# Digispark_Neopixel_Button_Cycler.net
KiCad netlist of a schematic drawn in EAGLE
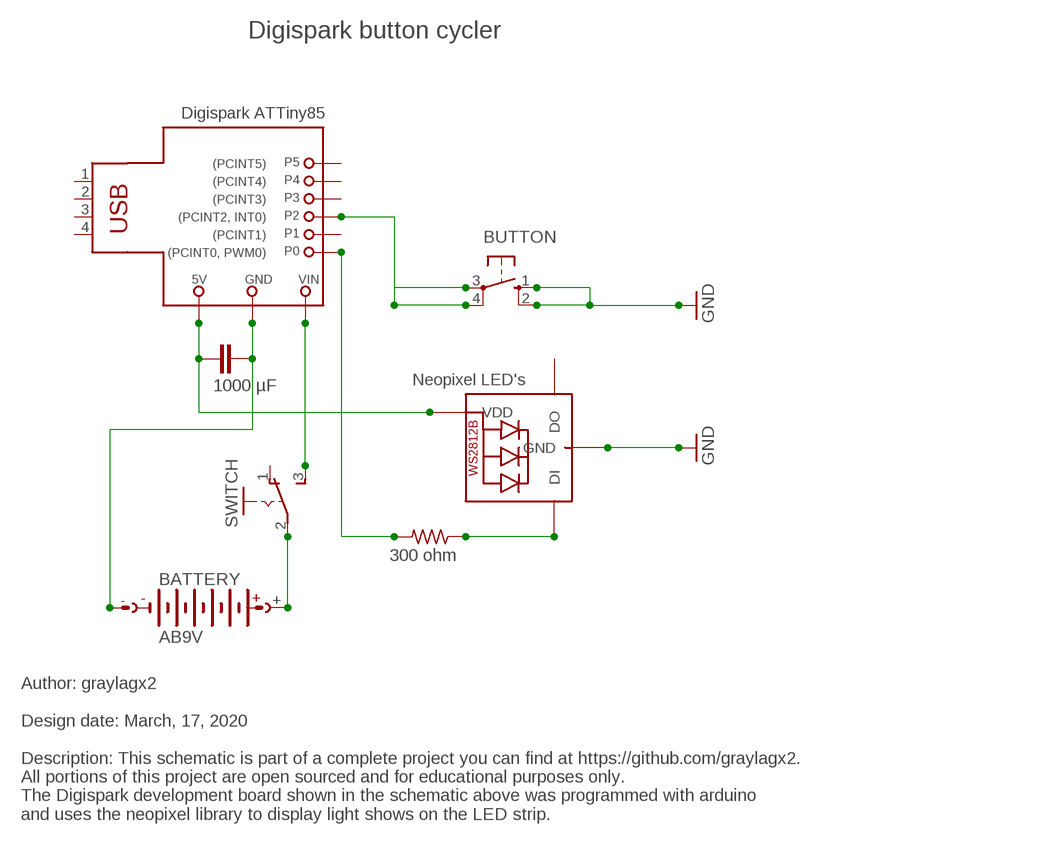
[diagram p0: schematic, sheet 1]

(export (version "E")
  (design (tool "Eeschema 10.0.6"))
  (components
    (comp (ref "BATTERY")
      (value "AB9V")
      (footprint "eagle-import:AB9V")
      (libsource (lib "eagle-import") (part "AB9V"))
    )
    (comp (ref "BUTTON")
      (value "10-XX")
      (footprint "eagle-import:B3F-10XX")
      (fields (field (name "MPN") "B3F-1000"))
      (libsource (lib "eagle-import") (part "10-XX"))
    )
    (comp (ref "C1")
      (value "1000 µF")
      (footprint "eagle-import:C2.5-2")
      (libsource (lib "eagle-import") (part "C2.5/2"))
    )
    (comp (ref "LED1")
      (value "WS2812B5050")
      (footprint "eagle-import:WS2812B")
      (libsource (lib "eagle-import") (part "WS2812B5050"))
    )
    (comp (ref "R1")
      (value "300 ohm")
      (footprint "eagle-import:0207_12")
      (libsource (lib "eagle-import") (part "R-US_0207/12"))
    )
    (comp (ref "SWITCH")
      (value "255SB")
      (footprint "eagle-import:255SB")
      (libsource (lib "eagle-import") (part "255SB"))
    )
    (comp (ref "X1")
      (value "PN87520")
      (footprint "eagle-import:PN87520")
      (libsource (lib "eagle-import") (part "PN87520"))
    )
  )
  (nets
    (net (code "1") (name "GND") (class "Default")
      (node (ref "BUTTON") (pin "1") (pinfunction "S_1") (pintype "passive"))
      (node (ref "BUTTON") (pin "2") (pinfunction "S1_2") (pintype "passive"))
      (node (ref "LED1") (pin "3-GND") (pinfunction "GND_3-GND") (pintype "power_in"))
    )
    (net (code "2") (name "Net-(BATTERY-Pad-)") (class "Default")
      (node (ref "BATTERY") (pin "-") (pinfunction "-_-") (pintype "passive"))
      (node (ref "C1") (pin "1") (pinfunction "1_1") (pintype "passive"))
    )
    (net (code "3") (name "Net-(BUTTON-P)") (class "Default")
      (node (ref "BUTTON") (pin "3") (pinfunction "P_3") (pintype "passive"))
      (node (ref "BUTTON") (pin "4") (pinfunction "P1_4") (pintype "passive"))
    )
    (net (code "4") (name "Net-(LED1-DI)") (class "Default")
      (node (ref "LED1") (pin "4-DIN") (pinfunction "DI_4-DIN") (pintype "input"))
      (node (ref "R1") (pin "1") (pinfunction "1_1") (pintype "passive"))
    )
    (net (code "5") (name "Net-(LED1-VDD)") (class "Default")
      (node (ref "C1") (pin "2") (pinfunction "2_2") (pintype "passive"))
      (node (ref "LED1") (pin "1-VDD") (pinfunction "VDD_1-VDD") (pintype "power_in"))
    )
    (net (code "6") (name "Net-(SWITCH-P)") (class "Default")
      (node (ref "BATTERY") (pin "+") (pinfunction "+_+") (pintype "passive"))
      (node (ref "SWITCH") (pin "2") (pinfunction "P_2") (pintype "passive"))
    )
    (net (code "7") (name "unconnected-(LED1-DO-Pad2-DOUT)") (class "Default")
      (node (ref "LED1") (pin "2-DOUT") (pinfunction "DO_2-DOUT") (pintype "output"))
    )
    (net (code "8") (name "unconnected-(R1-Pad2)") (class "Default")
      (node (ref "R1") (pin "2") (pinfunction "2_2") (pintype "passive"))
    )
    (net (code "9") (name "unconnected-(SWITCH-O-Pad1)") (class "Default")
      (node (ref "SWITCH") (pin "1") (pinfunction "O_1") (pintype "passive"))
    )
    (net (code "10") (name "unconnected-(SWITCH-S-Pad3)") (class "Default")
      (node (ref "SWITCH") (pin "3") (pinfunction "S_3") (pintype "passive"))
    )
    (net (code "11") (name "unconnected-(X1-Pad1)") (class "Default")
      (node (ref "X1") (pin "1") (pinfunction "1_1") (pintype "passive"))
    )
    (net (code "12") (name "unconnected-(X1-Pad2)") (class "Default")
      (node (ref "X1") (pin "2") (pinfunction "2_2") (pintype "passive"))
    )
    (net (code "13") (name "unconnected-(X1-Pad3)") (class "Default")
      (node (ref "X1") (pin "3") (pinfunction "3_3") (pintype "passive"))
    )
    (net (code "14") (name "unconnected-(X1-Pad4)") (class "Default")
      (node (ref "X1") (pin "4") (pinfunction "4_4") (pintype "passive"))
    )
  )
)
